# Task2.net
KiCad netlist of a schematic drawn in EAGLE
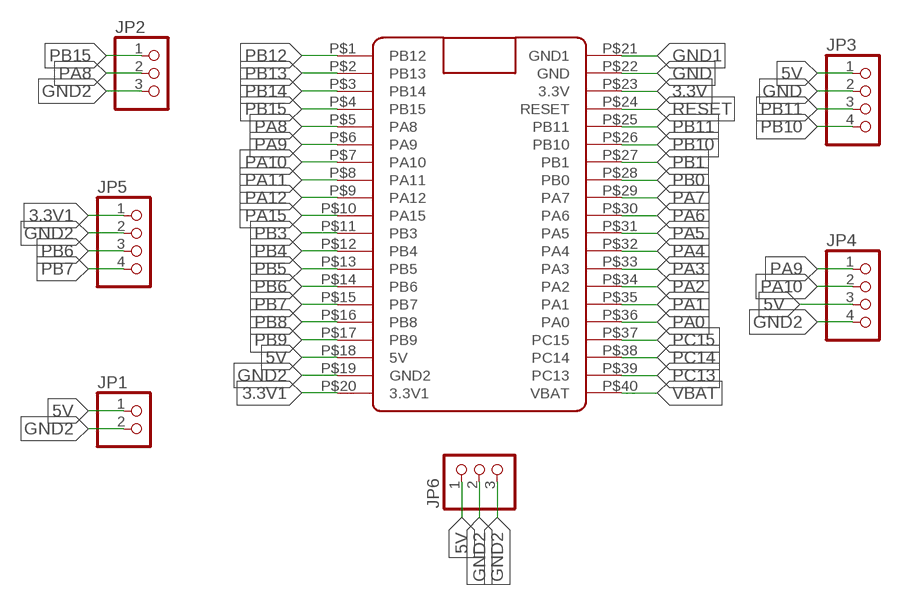
[diagram p0: schematic, sheet 1]

(export (version "E")
  (design (tool "Eeschema 10.0.6"))
  (components
    (comp (ref "JP1")
      (value "PINHD-1X2")
      (footprint "eagle-import:1X02")
      (libsource (lib "eagle-import") (part "PINHD-1X2"))
    )
    (comp (ref "JP2")
      (value "PINHD-1X3")
      (footprint "eagle-import:1X03")
      (libsource (lib "eagle-import") (part "PINHD-1X3"))
    )
    (comp (ref "JP3")
      (value "PINHD-1X4")
      (footprint "eagle-import:1X04")
      (libsource (lib "eagle-import") (part "PINHD-1X4"))
    )
    (comp (ref "JP4")
      (value "PINHD-1X4")
      (footprint "eagle-import:1X04")
      (libsource (lib "eagle-import") (part "PINHD-1X4"))
    )
    (comp (ref "JP5")
      (value "PINHD-1X4")
      (footprint "eagle-import:1X04")
      (libsource (lib "eagle-import") (part "PINHD-1X4"))
    )
    (comp (ref "JP6")
      (value "PINHD-1X3")
      (footprint "eagle-import:1X03")
      (libsource (lib "eagle-import") (part "PINHD-1X3"))
    )
    (comp (ref "U$1")
      (value "BLUE_PILL")
      (footprint "eagle-import:BLUE_PILL")
      (libsource (lib "eagle-import") (part "BLUE_PILL"))
    )
  )
  (nets
    (net (code "1") (name "3.3V") (class "Default")
      (node (ref "U$1") (pin "P$23") (pinfunction "3.3V_P$23") (pintype "bidirectional"))
    )
    (net (code "2") (name "3.3V1") (class "Default")
      (node (ref "JP5") (pin "1") (pinfunction "1_1") (pintype "passive"))
      (node (ref "U$1") (pin "P$20") (pinfunction "3.3V1_P$20") (pintype "bidirectional"))
    )
    (net (code "3") (name "5V") (class "Default")
      (node (ref "JP1") (pin "1") (pinfunction "1_1") (pintype "passive"))
      (node (ref "JP3") (pin "1") (pinfunction "1_1") (pintype "passive"))
      (node (ref "JP4") (pin "3") (pinfunction "3_3") (pintype "passive"))
      (node (ref "JP6") (pin "1") (pinfunction "1_1") (pintype "passive"))
      (node (ref "U$1") (pin "P$18") (pinfunction "5V_P$18") (pintype "bidirectional"))
    )
    (net (code "4") (name "GND") (class "Default")
      (node (ref "JP3") (pin "2") (pinfunction "2_2") (pintype "passive"))
      (node (ref "U$1") (pin "P$22") (pinfunction "GND_P$22") (pintype "bidirectional"))
    )
    (net (code "5") (name "GND1") (class "Default")
      (node (ref "U$1") (pin "P$21") (pinfunction "GND1_P$21") (pintype "power_in"))
    )
    (net (code "6") (name "GND2") (class "Default")
      (node (ref "JP1") (pin "2") (pinfunction "2_2") (pintype "passive"))
      (node (ref "JP2") (pin "3") (pinfunction "3_3") (pintype "passive"))
      (node (ref "JP4") (pin "4") (pinfunction "4_4") (pintype "passive"))
      (node (ref "JP5") (pin "2") (pinfunction "2_2") (pintype "passive"))
      (node (ref "JP6") (pin "2") (pinfunction "2_2") (pintype "passive"))
      (node (ref "JP6") (pin "3") (pinfunction "3_3") (pintype "passive"))
      (node (ref "U$1") (pin "P$19") (pinfunction "GND2_P$19") (pintype "bidirectional"))
    )
    (net (code "7") (name "PA0") (class "Default")
      (node (ref "U$1") (pin "P$36") (pinfunction "PA0_P$36") (pintype "bidirectional"))
    )
    (net (code "8") (name "PA1") (class "Default")
      (node (ref "U$1") (pin "P$35") (pinfunction "PA1_P$35") (pintype "bidirectional"))
    )
    (net (code "9") (name "PA2") (class "Default")
      (node (ref "U$1") (pin "P$34") (pinfunction "PA2_P$34") (pintype "bidirectional"))
    )
    (net (code "10") (name "PA3") (class "Default")
      (node (ref "U$1") (pin "P$33") (pinfunction "PA3_P$33") (pintype "bidirectional"))
    )
    (net (code "11") (name "PA4") (class "Default")
      (node (ref "U$1") (pin "P$32") (pinfunction "PA4_P$32") (pintype "bidirectional"))
    )
    (net (code "12") (name "PA5") (class "Default")
      (node (ref "U$1") (pin "P$31") (pinfunction "PA5_P$31") (pintype "bidirectional"))
    )
    (net (code "13") (name "PA6") (class "Default")
      (node (ref "U$1") (pin "P$30") (pinfunction "PA6_P$30") (pintype "bidirectional"))
    )
    (net (code "14") (name "PA7") (class "Default")
      (node (ref "U$1") (pin "P$29") (pinfunction "PA7_P$29") (pintype "bidirectional"))
    )
    (net (code "15") (name "PA8") (class "Default")
      (node (ref "JP2") (pin "2") (pinfunction "2_2") (pintype "passive"))
      (node (ref "U$1") (pin "P$5") (pinfunction "PA8_P$5") (pintype "bidirectional"))
    )
    (net (code "16") (name "PA9") (class "Default")
      (node (ref "JP4") (pin "1") (pinfunction "1_1") (pintype "passive"))
      (node (ref "U$1") (pin "P$6") (pinfunction "PA9_P$6") (pintype "bidirectional"))
    )
    (net (code "17") (name "PA10") (class "Default")
      (node (ref "JP4") (pin "2") (pinfunction "2_2") (pintype "passive"))
      (node (ref "U$1") (pin "P$7") (pinfunction "PA10_P$7") (pintype "bidirectional"))
    )
    (net (code "18") (name "PA11") (class "Default")
      (node (ref "U$1") (pin "P$8") (pinfunction "PA11_P$8") (pintype "bidirectional"))
    )
    (net (code "19") (name "PA12") (class "Default")
      (node (ref "U$1") (pin "P$9") (pinfunction "PA12_P$9") (pintype "bidirectional"))
    )
    (net (code "20") (name "PA15") (class "Default")
      (node (ref "U$1") (pin "P$10") (pinfunction "PA15_P$10") (pintype "bidirectional"))
    )
    (net (code "21") (name "PB0") (class "Default")
      (node (ref "U$1") (pin "P$28") (pinfunction "PB0_P$28") (pintype "bidirectional"))
    )
    (net (code "22") (name "PB1") (class "Default")
      (node (ref "U$1") (pin "P$27") (pinfunction "PB1_P$27") (pintype "bidirectional"))
    )
    (net (code "23") (name "PB3") (class "Default")
      (node (ref "U$1") (pin "P$11") (pinfunction "PB3_P$11") (pintype "bidirectional"))
    )
    (net (code "24") (name "PB4") (class "Default")
      (node (ref "U$1") (pin "P$12") (pinfunction "PB4_P$12") (pintype "bidirectional"))
    )
    (net (code "25") (name "PB5") (class "Default")
      (node (ref "U$1") (pin "P$13") (pinfunction "PB5_P$13") (pintype "bidirectional"))
    )
    (net (code "26") (name "PB6") (class "Default")
      (node (ref "JP5") (pin "3") (pinfunction "3_3") (pintype "passive"))
      (node (ref "U$1") (pin "P$14") (pinfunction "PB6_P$14") (pintype "bidirectional"))
    )
    (net (code "27") (name "PB7") (class "Default")
      (node (ref "JP5") (pin "4") (pinfunction "4_4") (pintype "passive"))
      (node (ref "U$1") (pin "P$15") (pinfunction "PB7_P$15") (pintype "bidirectional"))
    )
    (net (code "28") (name "PB8") (class "Default")
      (node (ref "U$1") (pin "P$16") (pinfunction "PB8_P$16") (pintype "bidirectional"))
    )
    (net (code "29") (name "PB9") (class "Default")
      (node (ref "U$1") (pin "P$17") (pinfunction "PB9_P$17") (pintype "bidirectional"))
    )
    (net (code "30") (name "PB10") (class "Default")
      (node (ref "JP3") (pin "4") (pinfunction "4_4") (pintype "passive"))
      (node (ref "U$1") (pin "P$26") (pinfunction "PB10_P$26") (pintype "bidirectional"))
    )
    (net (code "31") (name "PB11") (class "Default")
      (node (ref "JP3") (pin "3") (pinfunction "3_3") (pintype "passive"))
      (node (ref "U$1") (pin "P$25") (pinfunction "PB11_P$25") (pintype "bidirectional"))
    )
    (net (code "32") (name "PB12") (class "Default")
      (node (ref "U$1") (pin "P$1") (pinfunction "PB12_P$1") (pintype "bidirectional"))
    )
    (net (code "33") (name "PB13") (class "Default")
      (node (ref "U$1") (pin "P$2") (pinfunction "PB13_P$2") (pintype "bidirectional"))
    )
    (net (code "34") (name "PB14") (class "Default")
      (node (ref "U$1") (pin "P$3") (pinfunction "PB14_P$3") (pintype "bidirectional"))
    )
    (net (code "35") (name "PB15") (class "Default")
      (node (ref "JP2") (pin "1") (pinfunction "1_1") (pintype "passive"))
      (node (ref "U$1") (pin "P$4") (pinfunction "PB15_P$4") (pintype "bidirectional"))
    )
    (net (code "36") (name "PC13") (class "Default")
      (node (ref "U$1") (pin "P$39") (pinfunction "PC13_P$39") (pintype "bidirectional"))
    )
    (net (code "37") (name "PC14") (class "Default")
      (node (ref "U$1") (pin "P$38") (pinfunction "PC14_P$38") (pintype "bidirectional"))
    )
    (net (code "38") (name "PC15") (class "Default")
      (node (ref "U$1") (pin "P$37") (pinfunction "PC15_P$37") (pintype "bidirectional"))
    )
    (net (code "39") (name "RESET") (class "Default")
      (node (ref "U$1") (pin "P$24") (pinfunction "RESET_P$24") (pintype "bidirectional"))
    )
    (net (code "40") (name "VBAT") (class "Default")
      (node (ref "U$1") (pin "P$40") (pinfunction "VBAT_P$40") (pintype "bidirectional"))
    )
  )
)
